# 001_top.net
KiCad netlist of a schematic drawn in Altium Designer
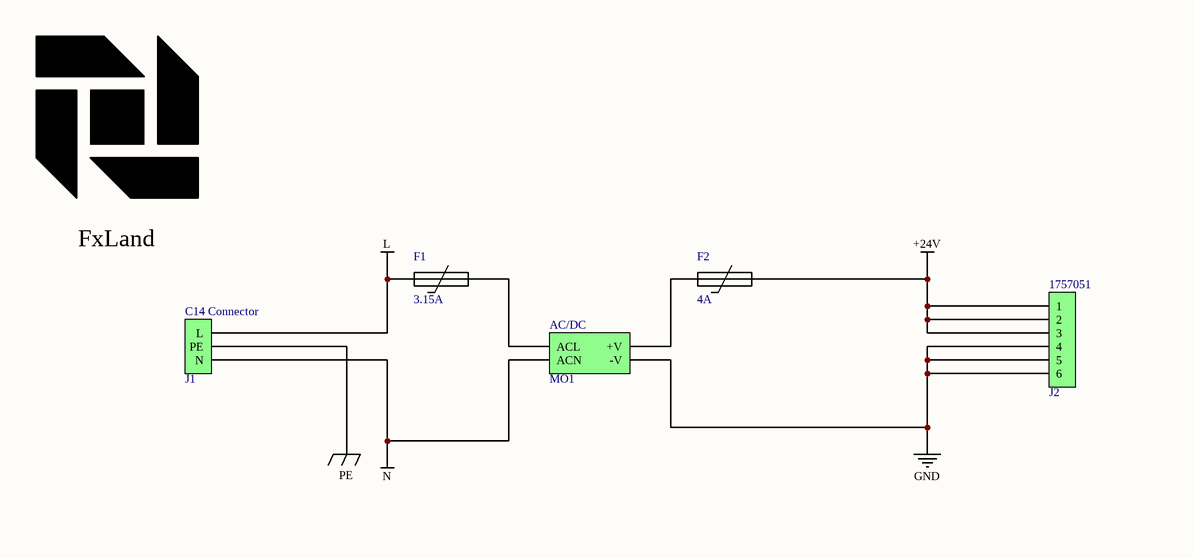
[diagram p0: 001_top.SchDoc, left]
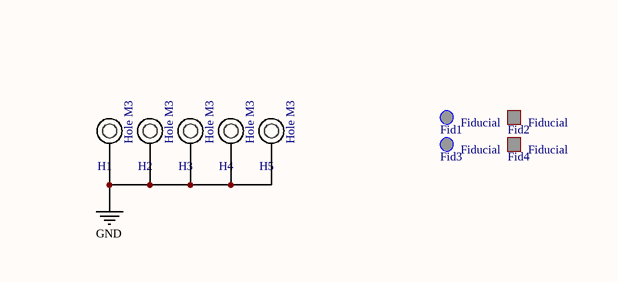
[diagram p1: 001_top.SchDoc, right]

(export (version "E")
  (design (tool "Eeschema 10.0.6"))
  (components
    (comp (ref "F1")
      (value "3.15A")
      (footprint "Lead2INCHSqaure")
      (description "AC 3.15A")
      (fields
        (field (name "REFVAL") "3.15A")
        (field (name "PART NUMBER") "F0003")
        (field (name "MANFACTPART") "0697A3150-01")
      )
      (libsource (lib "GTS_Database") (part "F"))
    )
    (comp (ref "F2")
      (value "4A")
      (footprint "F1206")
      (description "65V/4A")
      (fields
        (field (name "REFVAL") "4A")
        (field (name "PART NUMBER") "F0013")
        (field (name "MANFACTPART") "SF-1206SA400M-2")
      )
      (libsource (lib "GTS_Database") (part "F"))
    )
    (comp (ref "Fid1")
      (value "Fiducial")
      (footprint "FidR_1.0mm")
      (description "Fiducial Round 1mm")
      (fields (field (name "REFVAL") "Fiducial") (field (name "PART NUMBER") "ME0011"))
      (libsource (lib "GTS_Database") (part "FidR_1.0mm"))
    )
    (comp (ref "Fid2")
      (value "Fiducial")
      (footprint "FidS_1.0mm")
      (description "Fiducial Sqaure 1mm")
      (fields (field (name "REFVAL") "Fiducial") (field (name "PART NUMBER") "ME0012"))
      (libsource (lib "GTS_Database") (part "FidS_1.0mm"))
    )
    (comp (ref "Fid3")
      (value "Fiducial")
      (footprint "FidR_1.0mm")
      (description "Fiducial Round 1mm")
      (fields (field (name "REFVAL") "Fiducial") (field (name "PART NUMBER") "ME0011"))
      (libsource (lib "GTS_Database") (part "FidR_1.0mm"))
    )
    (comp (ref "Fid4")
      (value "Fiducial")
      (footprint "FidS_1.0mm")
      (description "Fiducial Sqaure 1mm")
      (fields (field (name "REFVAL") "Fiducial") (field (name "PART NUMBER") "ME0012"))
      (libsource (lib "GTS_Database") (part "FidS_1.0mm"))
    )
    (comp (ref "H1")
      (value "Hole M3")
      (footprint "HOLE_M3")
      (description "Mounting Hole M3")
      (fields (field (name "REFVAL") "Hole M3") (field (name "PART NUMBER") "ME0001"))
      (libsource (lib "GTS_Database") (part "HOLE"))
    )
    (comp (ref "H2")
      (value "Hole M3")
      (footprint "HOLE_M3")
      (description "Mounting Hole M3")
      (fields (field (name "REFVAL") "Hole M3") (field (name "PART NUMBER") "ME0001"))
      (libsource (lib "GTS_Database") (part "HOLE"))
    )
    (comp (ref "H3")
      (value "Hole M3")
      (footprint "HOLE_M3")
      (description "Mounting Hole M3")
      (fields (field (name "REFVAL") "Hole M3") (field (name "PART NUMBER") "ME0001"))
      (libsource (lib "GTS_Database") (part "HOLE"))
    )
    (comp (ref "H4")
      (value "Hole M3")
      (footprint "HOLE_M3")
      (description "Mounting Hole M3")
      (fields (field (name "REFVAL") "Hole M3") (field (name "PART NUMBER") "ME0001"))
      (libsource (lib "GTS_Database") (part "HOLE"))
    )
    (comp (ref "H5")
      (value "Hole M3")
      (footprint "HOLE_M3")
      (description "Mounting Hole M3")
      (fields (field (name "REFVAL") "Hole M3") (field (name "PART NUMBER") "ME0001"))
      (libsource (lib "GTS_Database") (part "HOLE"))
    )
    (comp (ref "J1")
      (value "C14 Connector")
      (footprint "IEC_INLET_PX0575SERIES")
      (fields
        (field (name "REFVAL") "C14 Connector")
        (field (name "PART NUMBER") "CO0038")
        (field (name "MANFACTPART") "PX0575/10/PC")
      )
      (libsource (lib "GTS_Database") (part "AC_Inlet"))
    )
    (comp (ref "J2")
      (value "1757051")
      (footprint "1757051")
      (description "Pluggable Terminal Blocks 6 Pos 5.08mm pitch Plug 24-12 AWG Screw")
      (fields (field (name "REFVAL") "1757051") (field (name "PART NUMBER") "CO0034"))
      (libsource (lib "GTS_Database") (part "CONN1X6P"))
    )
    (comp (ref "Logo FxLand")
      (value "FxLand")
      (footprint "Logo_FxLand_3")
      (description "Logo FxLand 3")
      (fields (field (name "PART NUMBER") "ME0008"))
      (libsource (lib "GTS_Database") (part "Logo_FxLand_2"))
    )
    (comp (ref "MO1")
      (value "AC/DC")
      (footprint "ECE80")
      (description "AC-DC Power Supplies")
      (fields
        (field (name "REFVAL") "AC/DC")
        (field (name "PART NUMBER") "MO0021")
        (field (name "MANFACTPART") "ECE80US24")
      )
      (libsource (lib "GTS_Database") (part "ECE80"))
    )
  )
  (nets
    (net (code "1") (name "+24V") (class "Default")
      (node (ref "F2") (pin "2") (pinfunction "2_2") (pintype "passive"))
      (node (ref "J2") (pin "1") (pinfunction "1_1") (pintype "passive"))
      (node (ref "J2") (pin "2") (pinfunction "2_2") (pintype "passive"))
      (node (ref "J2") (pin "3") (pinfunction "3_3") (pintype "passive"))
    )
    (net (code "2") (name "GND") (class "Default")
      (node (ref "H1") (pin "1") (pinfunction "1_1") (pintype "passive"))
      (node (ref "H2") (pin "1") (pinfunction "1_1") (pintype "passive"))
      (node (ref "H3") (pin "1") (pinfunction "1_1") (pintype "passive"))
      (node (ref "H4") (pin "1") (pinfunction "1_1") (pintype "passive"))
      (node (ref "H5") (pin "1") (pinfunction "1_1") (pintype "passive"))
      (node (ref "J2") (pin "4") (pinfunction "4_4") (pintype "passive"))
      (node (ref "J2") (pin "5") (pinfunction "5_5") (pintype "passive"))
      (node (ref "J2") (pin "6") (pinfunction "6_6") (pintype "passive"))
      (node (ref "MO1") (pin "-V") (pinfunction "-V_-V") (pintype "passive"))
    )
    (net (code "3") (name "L") (class "Default")
      (node (ref "F1") (pin "1") (pinfunction "1_1") (pintype "passive"))
      (node (ref "J1") (pin "1") (pinfunction "L_1") (pintype "passive"))
    )
    (net (code "4") (name "N") (class "Default")
      (node (ref "J1") (pin "3") (pinfunction "N_3") (pintype "passive"))
      (node (ref "MO1") (pin "ACN") (pinfunction "ACN_ACN") (pintype "passive"))
    )
    (net (code "5") (name "Net-(F1-Pad2)") (class "Default")
      (node (ref "F1") (pin "2") (pinfunction "2_2") (pintype "passive"))
      (node (ref "MO1") (pin "ACL") (pinfunction "ACL_ACL") (pintype "passive"))
    )
    (net (code "6") (name "Net-(F2-Pad1)") (class "Default")
      (node (ref "F2") (pin "1") (pinfunction "1_1") (pintype "passive"))
      (node (ref "MO1") (pin "+V") (pinfunction "+V_+V") (pintype "passive"))
    )
    (net (code "7") (name "PE") (class "Default")
      (node (ref "J1") (pin "2") (pinfunction "PE_2") (pintype "passive"))
    )
  )
)
